# McPiFace-TFT-V1.net
KiCad netlist of a schematic drawn in EAGLE
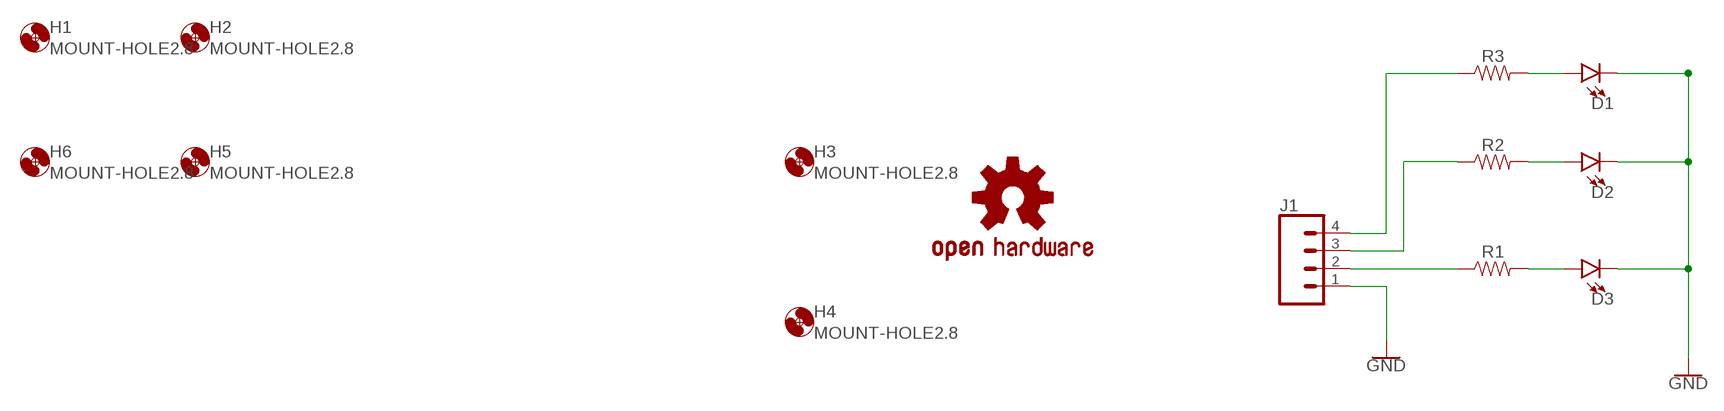
[diagram p0: schematic, sheet 1]

(export (version "E")
  (design (tool "Eeschema 10.0.6"))
  (components
    (comp (ref "D1")
      (value "LED1206-BOTTOM-1.6MM")
      (footprint "eagle-import:LED-1206-BOTTOM-1.6MM")
      (libsource (lib "eagle-import") (part "LED1206-BOTTOM-1.6MM"))
    )
    (comp (ref "D2")
      (value "LED1206-BOTTOM-1.6MM")
      (footprint "eagle-import:LED-1206-BOTTOM-1.6MM")
      (libsource (lib "eagle-import") (part "LED1206-BOTTOM-1.6MM"))
    )
    (comp (ref "D3")
      (value "LED1206-BOTTOM-1.6MM")
      (footprint "eagle-import:LED-1206-BOTTOM-1.6MM")
      (libsource (lib "eagle-import") (part "LED1206-BOTTOM-1.6MM"))
    )
    (comp (ref "H1")
      (value "MOUNT-HOLE2.8")
      (footprint "eagle-import:2,8")
      (libsource (lib "eagle-import") (part "MOUNT-HOLE2.8"))
    )
    (comp (ref "H2")
      (value "MOUNT-HOLE2.8")
      (footprint "eagle-import:2,8")
      (libsource (lib "eagle-import") (part "MOUNT-HOLE2.8"))
    )
    (comp (ref "H3")
      (value "MOUNT-HOLE2.8")
      (footprint "eagle-import:2,8")
      (libsource (lib "eagle-import") (part "holes_MOUNT-HOLE2.8"))
    )
    (comp (ref "H4")
      (value "MOUNT-HOLE2.8")
      (footprint "eagle-import:2,8")
      (libsource (lib "eagle-import") (part "holes_MOUNT-HOLE2.8"))
    )
    (comp (ref "H5")
      (value "MOUNT-HOLE2.8")
      (footprint "eagle-import:2,8")
      (libsource (lib "eagle-import") (part "MOUNT-HOLE2.8"))
    )
    (comp (ref "H6")
      (value "MOUNT-HOLE2.8")
      (footprint "eagle-import:2,8")
      (libsource (lib "eagle-import") (part "MOUNT-HOLE2.8"))
    )
    (comp (ref "J1")
      (value "CONN_04SMD2")
      (footprint "eagle-import:1X04_1MM_RA")
      (libsource (lib "eagle-import") (part "CONN_04SMD2"))
    )
    (comp (ref "LOGO1")
      (value "OSHW-LOGOL")
      (footprint "eagle-import:OSHW-LOGO-L")
      (libsource (lib "eagle-import") (part "OSHW-LOGOL"))
    )
    (comp (ref "R1")
      (value "RESISTOR1206")
      (footprint "eagle-import:1206")
      (libsource (lib "eagle-import") (part "RESISTOR1206"))
    )
    (comp (ref "R2")
      (value "RESISTOR1206")
      (footprint "eagle-import:1206")
      (libsource (lib "eagle-import") (part "RESISTOR1206"))
    )
    (comp (ref "R3")
      (value "RESISTOR1206")
      (footprint "eagle-import:1206")
      (libsource (lib "eagle-import") (part "RESISTOR1206"))
    )
  )
  (nets
    (net (code "1") (name "GND") (class "Default")
      (node (ref "D1") (pin "C") (pinfunction "C_C") (pintype "passive"))
      (node (ref "D2") (pin "C") (pinfunction "C_C") (pintype "passive"))
      (node (ref "D3") (pin "C") (pinfunction "C_C") (pintype "passive"))
      (node (ref "J1") (pin "1") (pinfunction "1_1") (pintype "passive"))
    )
    (net (code "2") (name "Net-(D1-PadA)") (class "Default")
      (node (ref "D1") (pin "A") (pinfunction "A_A") (pintype "passive"))
      (node (ref "R3") (pin "2") (pinfunction "2_2") (pintype "passive"))
    )
    (net (code "3") (name "Net-(D2-PadA)") (class "Default")
      (node (ref "D2") (pin "A") (pinfunction "A_A") (pintype "passive"))
      (node (ref "R2") (pin "2") (pinfunction "2_2") (pintype "passive"))
    )
    (net (code "4") (name "Net-(D3-PadA)") (class "Default")
      (node (ref "D3") (pin "A") (pinfunction "A_A") (pintype "passive"))
      (node (ref "R1") (pin "2") (pinfunction "2_2") (pintype "passive"))
    )
    (net (code "5") (name "Net-(J1-Pad2)") (class "Default")
      (node (ref "J1") (pin "2") (pinfunction "2_2") (pintype "passive"))
      (node (ref "R1") (pin "1") (pinfunction "1_1") (pintype "passive"))
    )
    (net (code "6") (name "Net-(J1-Pad3)") (class "Default")
      (node (ref "J1") (pin "3") (pinfunction "3_3") (pintype "passive"))
      (node (ref "R2") (pin "1") (pinfunction "1_1") (pintype "passive"))
    )
    (net (code "7") (name "Net-(J1-Pad4)") (class "Default")
      (node (ref "J1") (pin "4") (pinfunction "4_4") (pintype "passive"))
      (node (ref "R3") (pin "1") (pinfunction "1_1") (pintype "passive"))
    )
  )
)
